# WIFI.net
KiCad netlist of a schematic drawn in Altium Designer
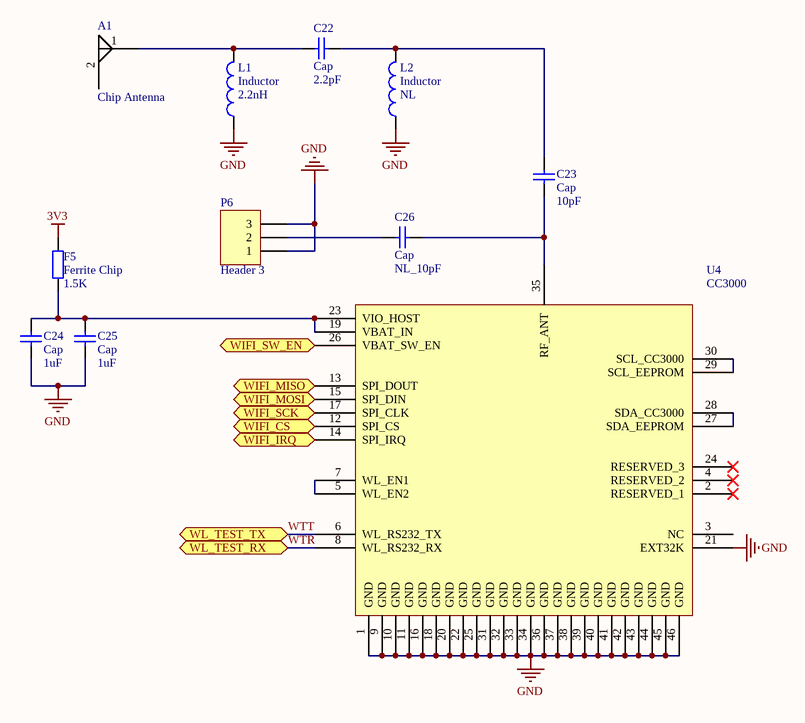
[diagram p0: WIFI.SchDoc]

(export (version "E")
  (design (tool "Eeschema 10.0.6"))
  (components
    (comp (ref "A1")
      (value "Chip Antenna")
      (footprint "2500AT44M0400")
      (libsource (lib "BrewBit") (part "ANT-SMT-2"))
    )
    (comp (ref "C22")
      (value "Cap")
      (footprint "0402")
      (description "Capacitor")
      (fields (field (name "ALTIUM_VALUE") "2.2pF"))
      (libsource (lib "Miscellaneous Devices") (part "Cap"))
    )
    (comp (ref "C23")
      (value "Cap")
      (footprint "0402")
      (description "Capacitor")
      (fields (field (name "ALTIUM_VALUE") "10pF"))
      (libsource (lib "Miscellaneous Devices") (part "Cap"))
    )
    (comp (ref "C24")
      (value "Cap")
      (footprint "0603")
      (description "Capacitor")
      (fields (field (name "ALTIUM_VALUE") "1uF"))
      (libsource (lib "Miscellaneous Devices") (part "Cap"))
    )
    (comp (ref "C25")
      (value "Cap")
      (footprint "0603")
      (description "Capacitor")
      (fields (field (name "ALTIUM_VALUE") "1uF"))
      (libsource (lib "Miscellaneous Devices") (part "Cap"))
    )
    (comp (ref "C26")
      (value "Cap")
      (footprint "0402")
      (description "Capacitor")
      (fields (field (name "ALTIUM_VALUE") "NL_10pF"))
      (libsource (lib "Miscellaneous Devices") (part "Cap"))
    )
    (comp (ref "F5")
      (value "Ferrite Chip")
      (footprint "0603")
      (fields (field (name "ALTIUM_VALUE") "1.5K"))
      (libsource (lib "Miscellaneous Devices") (part "Res2"))
    )
    (comp (ref "L1")
      (value "Inductor")
      (footprint "0402")
      (fields (field (name "ALTIUM_VALUE") "2.2nH"))
      (libsource (lib "Miscellaneous Devices") (part "Inductor"))
    )
    (comp (ref "L2")
      (value "Inductor")
      (footprint "0402")
      (fields (field (name "ALTIUM_VALUE") "NL"))
      (libsource (lib "Miscellaneous Devices") (part "Inductor"))
    )
    (comp (ref "P6")
      (value "Header 3")
      (footprint "U.FL-R-SMT-1")
      (description "Header, 3-Pin")
      (libsource (lib "Miscellaneous Connectors") (part "Header 3"))
    )
    (comp (ref "U4")
      (value "CC3000")
      (footprint "CC3000")
      (description "CC3000 WLAN Module")
      (libsource (lib "BrewBit") (part "CC3000"))
    )
  )
  (nets
    (net (code "1") (name "/WIFI_CS") (class "Default")
      (node (ref "U4") (pin "12") (pinfunction "SPI_CS_12") (pintype "passive"))
    )
    (net (code "2") (name "/WIFI_IRQ") (class "Default")
      (node (ref "U4") (pin "14") (pinfunction "SPI_IRQ_14") (pintype "passive"))
    )
    (net (code "3") (name "/WIFI_MISO") (class "Default")
      (node (ref "U4") (pin "13") (pinfunction "SPI_DOUT_13") (pintype "passive"))
    )
    (net (code "4") (name "/WIFI_MOSI") (class "Default")
      (node (ref "U4") (pin "15") (pinfunction "SPI_DIN_15") (pintype "passive"))
    )
    (net (code "5") (name "/WIFI_SCK") (class "Default")
      (node (ref "U4") (pin "17") (pinfunction "SPI_CLK_17") (pintype "passive"))
    )
    (net (code "6") (name "/WIFI_SW_EN") (class "Default")
      (node (ref "U4") (pin "26") (pinfunction "VBAT_SW_EN_26") (pintype "passive"))
    )
    (net (code "7") (name "/WTR") (class "Default")
      (node (ref "U4") (pin "8") (pinfunction "WL_RS232_RX_8") (pintype "passive"))
    )
    (net (code "8") (name "/WTT") (class "Default")
      (node (ref "U4") (pin "6") (pinfunction "WL_RS232_TX_6") (pintype "passive"))
    )
    (net (code "9") (name "3V3") (class "Default")
      (node (ref "F5") (pin "2") (pinfunction "2_2") (pintype "passive"))
    )
    (net (code "10") (name "GND") (class "Default")
      (node (ref "C24") (pin "1") (pinfunction "1_1") (pintype "passive"))
      (node (ref "C25") (pin "1") (pinfunction "1_1") (pintype "passive"))
      (node (ref "L1") (pin "1") (pinfunction "1_1") (pintype "passive"))
      (node (ref "L2") (pin "1") (pinfunction "1_1") (pintype "passive"))
      (node (ref "P6") (pin "1") (pinfunction "1_1") (pintype "passive"))
      (node (ref "P6") (pin "3") (pinfunction "3_3") (pintype "passive"))
      (node (ref "U4") (pin "1") (pinfunction "GND_1") (pintype "passive"))
      (node (ref "U4") (pin "10") (pinfunction "GND_10") (pintype "passive"))
      (node (ref "U4") (pin "11") (pinfunction "GND_11") (pintype "passive"))
      (node (ref "U4") (pin "16") (pinfunction "GND_16") (pintype "passive"))
      (node (ref "U4") (pin "18") (pinfunction "GND_18") (pintype "passive"))
      (node (ref "U4") (pin "20") (pinfunction "GND_20") (pintype "passive"))
      (node (ref "U4") (pin "21") (pinfunction "EXT32K_21") (pintype "passive"))
      (node (ref "U4") (pin "22") (pinfunction "GND_22") (pintype "passive"))
      (node (ref "U4") (pin "25") (pinfunction "GND_25") (pintype "passive"))
      (node (ref "U4") (pin "31") (pinfunction "GND_31") (pintype "passive"))
      (node (ref "U4") (pin "32") (pinfunction "GND_32") (pintype "passive"))
      (node (ref "U4") (pin "33") (pinfunction "GND_33") (pintype "passive"))
      (node (ref "U4") (pin "34") (pinfunction "GND_34") (pintype "passive"))
      (node (ref "U4") (pin "36") (pinfunction "GND_36") (pintype "passive"))
      (node (ref "U4") (pin "37") (pinfunction "GND_37") (pintype "passive"))
      (node (ref "U4") (pin "38") (pinfunction "GND_38") (pintype "passive"))
      (node (ref "U4") (pin "39") (pinfunction "GND_39") (pintype "passive"))
      (node (ref "U4") (pin "40") (pinfunction "GND_40") (pintype "passive"))
      (node (ref "U4") (pin "41") (pinfunction "GND_41") (pintype "passive"))
      (node (ref "U4") (pin "42") (pinfunction "GND_42") (pintype "passive"))
      (node (ref "U4") (pin "43") (pinfunction "GND_43") (pintype "passive"))
      (node (ref "U4") (pin "44") (pinfunction "GND_44") (pintype "passive"))
      (node (ref "U4") (pin "45") (pinfunction "GND_45") (pintype "passive"))
      (node (ref "U4") (pin "46") (pinfunction "GND_46") (pintype "passive"))
      (node (ref "U4") (pin "9") (pinfunction "GND_9") (pintype "passive"))
    )
    (net (code "11") (name "Net-(A1-Pad1)") (class "Default")
      (node (ref "A1") (pin "1") (pintype "passive"))
      (node (ref "C22") (pin "2") (pinfunction "2_2") (pintype "passive"))
      (node (ref "L1") (pin "2") (pinfunction "2_2") (pintype "passive"))
    )
    (net (code "12") (name "Net-(C22-Pad1)") (class "Default")
      (node (ref "C22") (pin "1") (pinfunction "1_1") (pintype "passive"))
      (node (ref "C23") (pin "2") (pinfunction "2_2") (pintype "passive"))
      (node (ref "L2") (pin "2") (pinfunction "2_2") (pintype "passive"))
    )
    (net (code "13") (name "Net-(C26-Pad2)") (class "Default")
      (node (ref "C26") (pin "2") (pinfunction "2_2") (pintype "passive"))
      (node (ref "P6") (pin "2") (pinfunction "2_2") (pintype "passive"))
    )
    (net (code "14") (name "Net-(U4-RF_ANT)") (class "Default")
      (node (ref "C23") (pin "1") (pinfunction "1_1") (pintype "passive"))
      (node (ref "C26") (pin "1") (pinfunction "1_1") (pintype "passive"))
      (node (ref "U4") (pin "35") (pinfunction "RF_ANT_35") (pintype "passive"))
    )
    (net (code "15") (name "Net-(U4-SCL_CC3000)") (class "Default")
      (node (ref "U4") (pin "29") (pinfunction "SCL_EEPROM_29") (pintype "passive"))
      (node (ref "U4") (pin "30") (pinfunction "SCL_CC3000_30") (pintype "passive"))
    )
    (net (code "16") (name "Net-(U4-SDA_CC3000)") (class "Default")
      (node (ref "U4") (pin "27") (pinfunction "SDA_EEPROM_27") (pintype "passive"))
      (node (ref "U4") (pin "28") (pinfunction "SDA_CC3000_28") (pintype "passive"))
    )
    (net (code "17") (name "Net-(U4-VBAT_IN)") (class "Default")
      (node (ref "C24") (pin "2") (pinfunction "2_2") (pintype "passive"))
      (node (ref "C25") (pin "2") (pinfunction "2_2") (pintype "passive"))
      (node (ref "F5") (pin "1") (pinfunction "1_1") (pintype "passive"))
      (node (ref "U4") (pin "19") (pinfunction "VBAT_IN_19") (pintype "passive"))
      (node (ref "U4") (pin "23") (pinfunction "VIO_HOST_23") (pintype "passive"))
    )
    (net (code "18") (name "Net-(U4-WL_EN1)") (class "Default")
      (node (ref "U4") (pin "5") (pinfunction "WL_EN2_5") (pintype "passive"))
      (node (ref "U4") (pin "7") (pinfunction "WL_EN1_7") (pintype "passive"))
    )
    (net (code "19") (name "unconnected-(A1-Pad2)") (class "Default")
      (node (ref "A1") (pin "2") (pintype "passive"))
    )
    (net (code "20") (name "unconnected-(U4-NC-Pad3)") (class "Default")
      (node (ref "U4") (pin "3") (pinfunction "NC_3") (pintype "passive"))
    )
    (net (code "21") (name "unconnected-(U4-RESERVED_1-Pad2)") (class "Default")
      (node (ref "U4") (pin "2") (pinfunction "RESERVED_1_2") (pintype "passive+no_connect"))
    )
    (net (code "22") (name "unconnected-(U4-RESERVED_2-Pad4)") (class "Default")
      (node (ref "U4") (pin "4") (pinfunction "RESERVED_2_4") (pintype "passive+no_connect"))
    )
    (net (code "23") (name "unconnected-(U4-RESERVED_3-Pad24)") (class "Default")
      (node (ref "U4") (pin "24") (pinfunction "RESERVED_3_24") (pintype "passive+no_connect"))
    )
  )
)
